# backlight_pwm_adapter.net
KiCad netlist of a schematic drawn in EAGLE
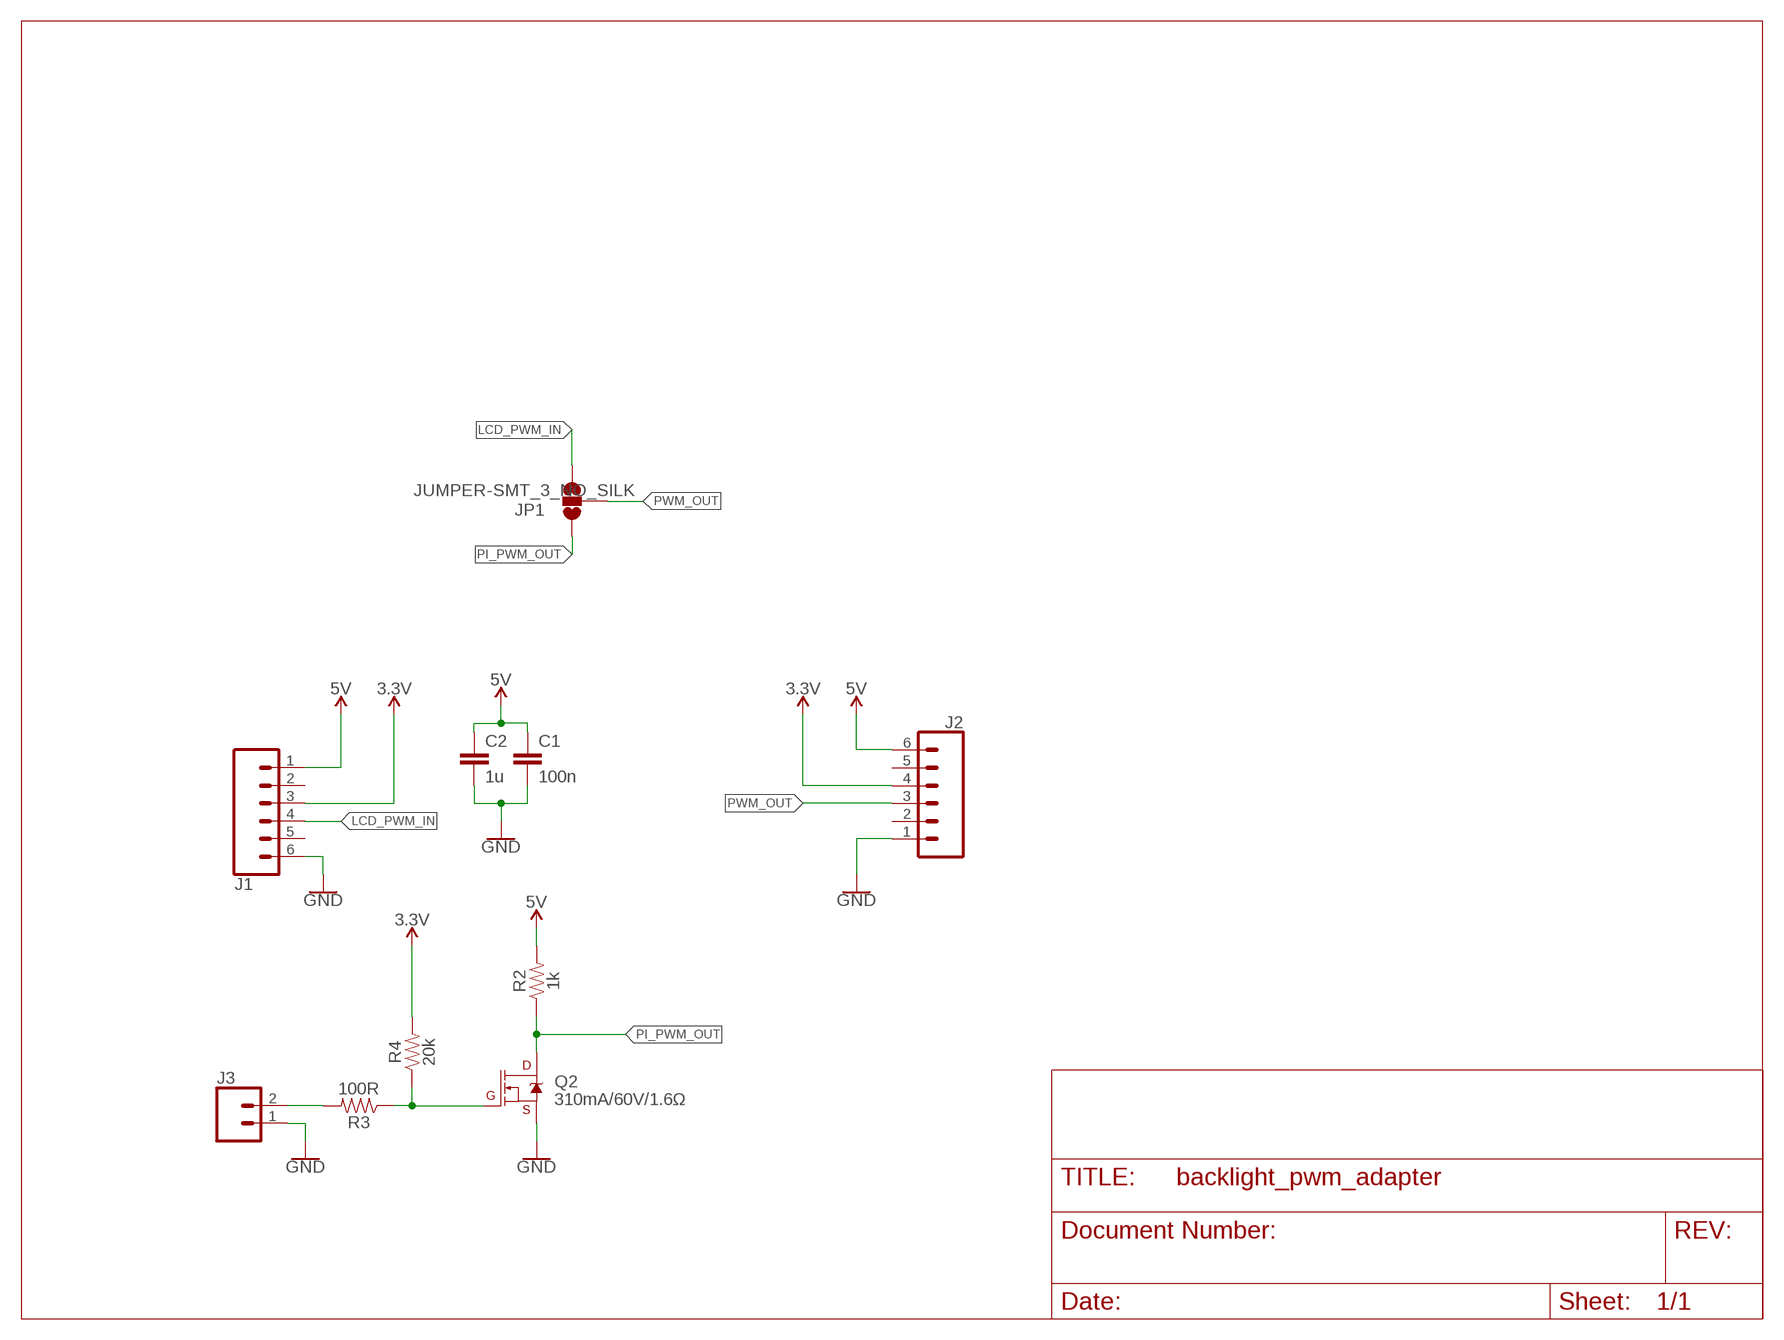
[diagram p0: schematic, sheet 1]

(export (version "E")
  (design (tool "Eeschema 10.0.6"))
  (components
    (comp (ref "C1")
      (value "100n")
      (footprint "eagle-import:0603")
      (fields (field (name "VOLTAGE") "50V"))
      (libsource (lib "eagle-import") (part "CL10B104MB8NNNC"))
    )
    (comp (ref "C2")
      (value "1u")
      (footprint "eagle-import:0603")
      (fields (field (name "VOLTAGE") "25V"))
      (libsource (lib "eagle-import") (part "CL10A105KA8NNNC"))
    )
    (comp (ref "J1")
      (value "CONN_06")
      (footprint "eagle-import:140-506-417-060")
      (libsource (lib "eagle-import") (part "CONN_06"))
    )
    (comp (ref "J2")
      (value "CONN_06")
      (footprint "eagle-import:140-506-417-060")
      (libsource (lib "eagle-import") (part "CONN_06"))
    )
    (comp (ref "J3")
      (value "CONN_02")
      (footprint "eagle-import:1X02")
      (libsource (lib "eagle-import") (part "CONN_02"))
    )
    (comp (ref "JP1")
      (value "JUMPER-SMT_3_NO_SILK")
      (footprint "eagle-import:SMT-JUMPER_3_NO_SILK")
      (libsource (lib "eagle-import") (part "JUMPER-SMT_3_NO_SILK"))
    )
    (comp (ref "Q2")
      (value "310mA/60V/1.6Ω")
      (footprint "eagle-import:SOT323")
      (libsource (lib "eagle-import") (part "MOSFET-NCH-2N7002PW"))
    )
    (comp (ref "R2")
      (value "1k")
      (footprint "eagle-import:0603")
      (libsource (lib "eagle-import") (part "RC0603JR-071KL"))
    )
    (comp (ref "R3")
      (value "100R")
      (footprint "eagle-import:0603")
      (libsource (lib "eagle-import") (part "RC0603JR-07100RL"))
    )
    (comp (ref "R4")
      (value "20k")
      (footprint "eagle-import:0603")
      (libsource (lib "eagle-import") (part "RC0603JR-0720KL"))
    )
  )
  (nets
    (net (code "1") (name "3.3V") (class "Default")
      (node (ref "J1") (pin "3") (pinfunction "3_3") (pintype "passive"))
      (node (ref "J2") (pin "4") (pinfunction "4_4") (pintype "passive"))
      (node (ref "R4") (pin "2") (pinfunction "2_2") (pintype "passive"))
    )
    (net (code "2") (name "5V") (class "Default")
      (node (ref "C1") (pin "1") (pinfunction "1_1") (pintype "passive"))
      (node (ref "C2") (pin "1") (pinfunction "1_1") (pintype "passive"))
      (node (ref "J1") (pin "1") (pinfunction "1_1") (pintype "passive"))
      (node (ref "J2") (pin "6") (pinfunction "6_6") (pintype "passive"))
      (node (ref "R2") (pin "2") (pinfunction "2_2") (pintype "passive"))
    )
    (net (code "3") (name "GND") (class "Default")
      (node (ref "C1") (pin "2") (pinfunction "2_2") (pintype "passive"))
      (node (ref "C2") (pin "2") (pinfunction "2_2") (pintype "passive"))
      (node (ref "J1") (pin "6") (pinfunction "6_6") (pintype "passive"))
      (node (ref "J2") (pin "1") (pinfunction "1_1") (pintype "passive"))
      (node (ref "J3") (pin "1") (pinfunction "1_1") (pintype "passive"))
      (node (ref "Q2") (pin "2") (pinfunction "S_2") (pintype "bidirectional"))
    )
    (net (code "4") (name "LCD_PWM_IN") (class "Default")
      (node (ref "J1") (pin "4") (pinfunction "4_4") (pintype "passive"))
      (node (ref "JP1") (pin "3") (pinfunction "3_3") (pintype "passive"))
    )
    (net (code "5") (name "Net-(J3-Pad2)") (class "Default")
      (node (ref "J3") (pin "2") (pinfunction "2_2") (pintype "passive"))
      (node (ref "R3") (pin "2") (pinfunction "2_2") (pintype "passive"))
    )
    (net (code "6") (name "Net-(Q2-G)") (class "Default")
      (node (ref "Q2") (pin "1") (pinfunction "G_1") (pintype "bidirectional"))
      (node (ref "R3") (pin "1") (pinfunction "1_1") (pintype "passive"))
      (node (ref "R4") (pin "1") (pinfunction "1_1") (pintype "passive"))
    )
    (net (code "7") (name "PI_PWM_OUT") (class "Default")
      (node (ref "JP1") (pin "1") (pinfunction "1_1") (pintype "passive"))
      (node (ref "Q2") (pin "3") (pinfunction "D_3") (pintype "bidirectional"))
      (node (ref "R2") (pin "1") (pinfunction "1_1") (pintype "passive"))
    )
    (net (code "8") (name "PWM_OUT") (class "Default")
      (node (ref "J2") (pin "3") (pinfunction "3_3") (pintype "passive"))
      (node (ref "JP1") (pin "2") (pinfunction "2_2") (pintype "passive"))
    )
    (net (code "9") (name "unconnected-(J1-Pad2)") (class "Default")
      (node (ref "J1") (pin "2") (pinfunction "2_2") (pintype "passive"))
    )
    (net (code "10") (name "unconnected-(J1-Pad5)") (class "Default")
      (node (ref "J1") (pin "5") (pinfunction "5_5") (pintype "passive"))
    )
    (net (code "11") (name "unconnected-(J2-Pad2)") (class "Default")
      (node (ref "J2") (pin "2") (pinfunction "2_2") (pintype "passive"))
    )
    (net (code "12") (name "unconnected-(J2-Pad5)") (class "Default")
      (node (ref "J2") (pin "5") (pinfunction "5_5") (pintype "passive"))
    )
  )
)
